# 51D.net
KiCad netlist of a schematic drawn in Altium Designer
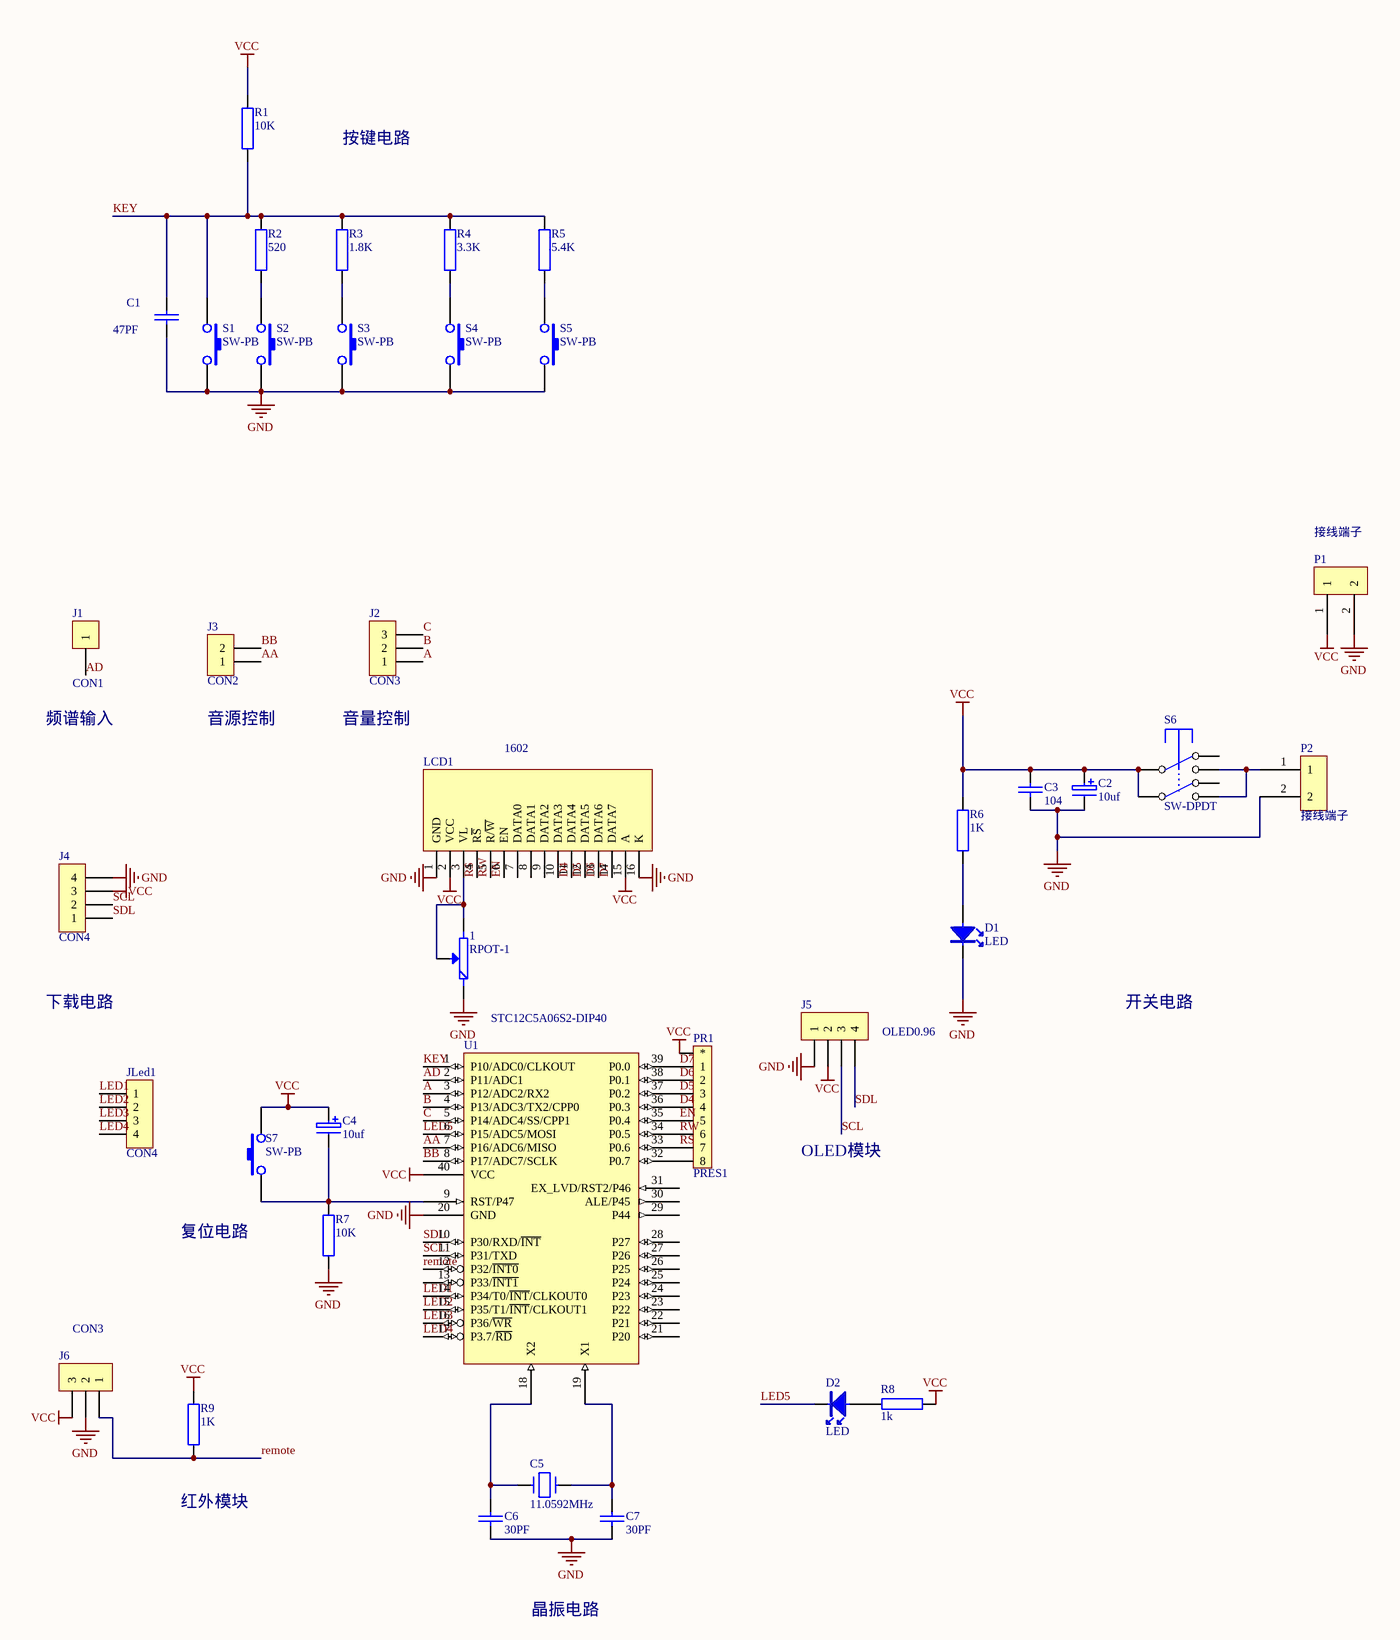
[diagram p0: 51D.SchDoc]

(export (version "E")
  (design (tool "Eeschema 10.0.6"))
  (components
    (comp (ref "1")
      (value "RPOT-1")
      (footprint "RVR-2")
      (description "普通电位器")
      (libsource (lib "电阻") (part "RPOT-1"))
    )
    (comp (ref "C1") (value "47PF") (footprint "CAP2") (libsource (lib "电容") (part "CAP1")))
    (comp (ref "C2") (value "10uf") (footprint "CAO2") (libsource (lib "电容") (part "CAP3")))
    (comp (ref "C3") (value "104") (footprint "CAP2") (libsource (lib "电容") (part "CAP1")))
    (comp (ref "C4") (value "10uf") (footprint "CAO2") (libsource (lib "电容") (part "CAP3")))
    (comp (ref "C5") (value "11.0592MHz") (footprint "XTAL1") (libsource (lib "晶振") (part "CPY")))
    (comp (ref "C6") (value "30PF") (footprint "CAP2") (libsource (lib "电容") (part "CAP1")))
    (comp (ref "C7") (value "30PF") (footprint "CAP2") (libsource (lib "电容") (part "CAP1")))
    (comp (ref "D1") (value "LED") (footprint "LED2_B") (libsource (lib "二极管") (part "LED")))
    (comp (ref "D2") (value "LED") (footprint "LED2_B") (libsource (lib "二极管") (part "LED")))
    (comp (ref "J1")
      (value "CON1")
      (footprint "SIP-1")
      (description "Connector")
      (libsource (lib "排针") (part "CON1"))
    )
    (comp (ref "J2")
      (value "CON3")
      (footprint "sip-3")
      (description "Connector")
      (libsource (lib "排针") (part "CON3"))
    )
    (comp (ref "J3")
      (value "CON2")
      (footprint "sip-2")
      (description "Connector")
      (libsource (lib "排针") (part "CON2"))
    )
    (comp (ref "J4")
      (value "CON4")
      (footprint "sip-4")
      (description "Connector")
      (libsource (lib "排针") (part "CON4"))
    )
    (comp (ref "J5")
      (value "OLED0.96")
      (footprint "sip-4")
      (description "Connector")
      (libsource (lib "") (part "CON4_1"))
    )
    (comp (ref "J6")
      (value "CON3")
      (footprint "sip-3")
      (description "Connector")
      (libsource (lib "") (part "CON3_1"))
    )
    (comp (ref "JLed1")
      (value "CON4")
      (footprint "sip-4")
      (description "Connector")
      (libsource (lib "") (part "CON4_2"))
    )
    (comp (ref "LCD1") (value "1602") (footprint "1602") (libsource (lib "液晶_数码管") (part "1602")))
    (comp (ref "P1") (value "接线端子") (footprint "音频功放自画库:接线端子") (libsource (lib "") (part "接线端子_1")))
    (comp (ref "P2") (value "接线端子") (footprint "音频功放自画库:接线端子") (libsource (lib "音频功放自画库") (part "接线端子")))
    (comp (ref "PR1") (value "PRES1") (footprint "RP1") (libsource (lib "电阻") (part "PRES1")))
    (comp (ref "R1")
      (value "10K")
      (footprint "AXIAL0.4")
      (description "电阻")
      (libsource (lib "电阻") (part "RES"))
    )
    (comp (ref "R2")
      (value "520")
      (footprint "AXIAL0.4")
      (description "电阻")
      (libsource (lib "电阻") (part "RES"))
    )
    (comp (ref "R3")
      (value "1.8K")
      (footprint "AXIAL0.4")
      (description "电阻")
      (libsource (lib "电阻") (part "RES"))
    )
    (comp (ref "R4")
      (value "3.3K")
      (footprint "AXIAL0.4")
      (description "电阻")
      (libsource (lib "电阻") (part "RES"))
    )
    (comp (ref "R5")
      (value "5.4K")
      (footprint "AXIAL0.4")
      (description "电阻")
      (libsource (lib "电阻") (part "RES"))
    )
    (comp (ref "R6")
      (value "1K")
      (footprint "AXIAL0.4")
      (description "电阻")
      (libsource (lib "电阻") (part "RES"))
    )
    (comp (ref "R7")
      (value "10K")
      (footprint "AXIAL0.4")
      (description "电阻")
      (libsource (lib "电阻") (part "RES"))
    )
    (comp (ref "R8")
      (value "1k")
      (footprint "AXIAL0.4")
      (description "电阻")
      (libsource (lib "电阻") (part "RES"))
    )
    (comp (ref "R9")
      (value "1K")
      (footprint "AXIAL0.4")
      (description "电阻")
      (libsource (lib "电阻") (part "RES"))
    )
    (comp (ref "S1") (value "SW-PB") (footprint "SW6*6") (libsource (lib "开关") (part "SW-PB")))
    (comp (ref "S2") (value "SW-PB") (footprint "SW6*6") (libsource (lib "开关") (part "SW-PB")))
    (comp (ref "S3") (value "SW-PB") (footprint "SW6*6") (libsource (lib "开关") (part "SW-PB")))
    (comp (ref "S4") (value "SW-PB") (footprint "SW6*6") (libsource (lib "开关") (part "SW-PB")))
    (comp (ref "S5") (value "SW-PB") (footprint "SW6*6") (libsource (lib "开关") (part "SW-PB")))
    (comp (ref "S6") (value "SW-DPDT") (footprint "SWH8*8") (libsource (lib "开关") (part "SW-DPDT")))
    (comp (ref "S7") (value "SW-PB") (footprint "SW6*6") (libsource (lib "开关") (part "SW-PB")))
    (comp (ref "U1")
      (value "STC12C5A06S2-DIP40")
      (footprint "DIP-40")
      (libsource (lib "单片机") (part "STC12C5A06S2-DIP40"))
    )
  )
  (nets
    (net (code "1") (name "/A") (class "Default")
      (node (ref "J2") (pin "1") (pinfunction "1_1") (pintype "passive"))
      (node (ref "U1") (pin "3") (pinfunction "P12/ADC2/RX2_3") (pintype "bidirectional"))
    )
    (net (code "2") (name "/AA") (class "Default")
      (node (ref "J3") (pin "1") (pinfunction "1_1") (pintype "passive"))
      (node (ref "U1") (pin "7") (pinfunction "P16/ADC6/MISO_7") (pintype "bidirectional"))
    )
    (net (code "3") (name "/AD") (class "Default")
      (node (ref "J1") (pin "1") (pinfunction "1_1") (pintype "passive"))
      (node (ref "U1") (pin "2") (pinfunction "P11/ADC1_2") (pintype "bidirectional"))
    )
    (net (code "4") (name "/B") (class "Default")
      (node (ref "J2") (pin "2") (pinfunction "2_2") (pintype "passive"))
      (node (ref "U1") (pin "4") (pinfunction "P13/ADC3/TX2/CPP0_4") (pintype "bidirectional"))
    )
    (net (code "5") (name "/BB") (class "Default")
      (node (ref "J3") (pin "2") (pinfunction "2_2") (pintype "passive"))
      (node (ref "U1") (pin "8") (pinfunction "P17/ADC7/SCLK_8") (pintype "bidirectional"))
    )
    (net (code "6") (name "/C") (class "Default")
      (node (ref "J2") (pin "3") (pinfunction "3_3") (pintype "passive"))
      (node (ref "U1") (pin "5") (pinfunction "P14/ADC4/SS/CPP1_5") (pintype "bidirectional"))
    )
    (net (code "7") (name "/D4") (class "Default")
      (node (ref "LCD1") (pin "11") (pinfunction "DATA4_11") (pintype "passive"))
      (node (ref "PR1") (pin "5") (pinfunction "4_5") (pintype "passive"))
      (node (ref "U1") (pin "36") (pinfunction "P0.3_36") (pintype "bidirectional"))
    )
    (net (code "8") (name "/D5") (class "Default")
      (node (ref "LCD1") (pin "12") (pinfunction "DATA5_12") (pintype "passive"))
      (node (ref "PR1") (pin "4") (pinfunction "3_4") (pintype "passive"))
      (node (ref "U1") (pin "37") (pinfunction "P0.2_37") (pintype "bidirectional"))
    )
    (net (code "9") (name "/D6") (class "Default")
      (node (ref "LCD1") (pin "13") (pinfunction "DATA6_13") (pintype "passive"))
      (node (ref "PR1") (pin "3") (pinfunction "2_3") (pintype "passive"))
      (node (ref "U1") (pin "38") (pinfunction "P0.1_38") (pintype "bidirectional"))
    )
    (net (code "10") (name "/D7") (class "Default")
      (node (ref "LCD1") (pin "14") (pinfunction "DATA7_14") (pintype "passive"))
      (node (ref "PR1") (pin "2") (pinfunction "1_2") (pintype "passive"))
      (node (ref "U1") (pin "39") (pinfunction "P0.0_39") (pintype "bidirectional"))
    )
    (net (code "11") (name "/EN") (class "Default")
      (node (ref "LCD1") (pin "6") (pinfunction "EN_6") (pintype "passive"))
      (node (ref "PR1") (pin "6") (pinfunction "5_6") (pintype "passive"))
      (node (ref "U1") (pin "35") (pinfunction "P0.4_35") (pintype "bidirectional"))
    )
    (net (code "12") (name "/KEY") (class "Default")
      (node (ref "C1") (pin "1") (pinfunction "1_1") (pintype "passive"))
      (node (ref "R1") (pin "1") (pinfunction "1_1") (pintype "passive"))
      (node (ref "R2") (pin "2") (pinfunction "2_2") (pintype "passive"))
      (node (ref "R3") (pin "2") (pinfunction "2_2") (pintype "passive"))
      (node (ref "R4") (pin "2") (pinfunction "2_2") (pintype "passive"))
      (node (ref "R5") (pin "2") (pinfunction "2_2") (pintype "passive"))
      (node (ref "S1") (pin "1") (pinfunction "1_1") (pintype "passive"))
      (node (ref "U1") (pin "1") (pinfunction "P10/ADC0/CLKOUT_1") (pintype "bidirectional"))
    )
    (net (code "13") (name "/LED1") (class "Default")
      (node (ref "JLed1") (pin "1") (pinfunction "1_1") (pintype "passive"))
      (node (ref "U1") (pin "14") (pinfunction "P34/T0/~{INT}/CLKOUT0_14") (pintype "bidirectional"))
    )
    (net (code "14") (name "/LED2") (class "Default")
      (node (ref "JLed1") (pin "2") (pinfunction "2_2") (pintype "passive"))
      (node (ref "U1") (pin "15") (pinfunction "P35/T1/~{INT}/CLKOUT1_15") (pintype "bidirectional"))
    )
    (net (code "15") (name "/LED3") (class "Default")
      (node (ref "JLed1") (pin "3") (pinfunction "3_3") (pintype "passive"))
      (node (ref "U1") (pin "16") (pinfunction "P36/~{WR}_16") (pintype "bidirectional"))
    )
    (net (code "16") (name "/LED4") (class "Default")
      (node (ref "JLed1") (pin "4") (pinfunction "4_4") (pintype "passive"))
      (node (ref "U1") (pin "17") (pinfunction "P3.7/~{RD}_17") (pintype "bidirectional"))
    )
    (net (code "17") (name "/LED5") (class "Default")
      (node (ref "D2") (pin "2") (pinfunction "2_2") (pintype "passive"))
      (node (ref "U1") (pin "6") (pinfunction "P15/ADC5/MOSI_6") (pintype "bidirectional"))
    )
    (net (code "18") (name "/RS") (class "Default")
      (node (ref "LCD1") (pin "4") (pinfunction "R~{S}_4") (pintype "passive"))
      (node (ref "PR1") (pin "8") (pinfunction "7_8") (pintype "passive"))
      (node (ref "U1") (pin "33") (pinfunction "P0.6_33") (pintype "bidirectional"))
    )
    (net (code "19") (name "/RW") (class "Default")
      (node (ref "LCD1") (pin "5") (pinfunction "R/~{W}_5") (pintype "passive"))
      (node (ref "PR1") (pin "7") (pinfunction "6_7") (pintype "passive"))
      (node (ref "U1") (pin "34") (pinfunction "P0.5_34") (pintype "bidirectional"))
    )
    (net (code "20") (name "/SCL") (class "Default")
      (node (ref "J4") (pin "2") (pinfunction "2_2") (pintype "passive"))
      (node (ref "J5") (pin "3") (pinfunction "3_3") (pintype "passive"))
      (node (ref "U1") (pin "11") (pinfunction "P31/TXD_11") (pintype "bidirectional"))
    )
    (net (code "21") (name "/SDL") (class "Default")
      (node (ref "J4") (pin "1") (pinfunction "1_1") (pintype "passive"))
      (node (ref "J5") (pin "4") (pinfunction "4_4") (pintype "passive"))
      (node (ref "U1") (pin "10") (pinfunction "P30/RXD/~{INT}_10") (pintype "bidirectional"))
    )
    (net (code "22") (name "/remote") (class "Default")
      (node (ref "J6") (pin "1") (pinfunction "1_1") (pintype "passive"))
      (node (ref "R9") (pin "1") (pinfunction "1_1") (pintype "passive"))
      (node (ref "U1") (pin "12") (pinfunction "P32/~{INT0}_12") (pintype "bidirectional"))
    )
    (net (code "23") (name "GND") (class "Default")
      (node (ref "1") (pin "1") (pinfunction "1_1") (pintype "passive"))
      (node (ref "C1") (pin "2") (pinfunction "2_2") (pintype "passive"))
      (node (ref "C2") (pin "2") (pintype "passive"))
      (node (ref "C3") (pin "2") (pinfunction "2_2") (pintype "passive"))
      (node (ref "C6") (pin "2") (pinfunction "2_2") (pintype "passive"))
      (node (ref "C7") (pin "2") (pinfunction "2_2") (pintype "passive"))
      (node (ref "D1") (pin "2") (pinfunction "2_2") (pintype "passive"))
      (node (ref "J4") (pin "4") (pinfunction "4_4") (pintype "passive"))
      (node (ref "J5") (pin "1") (pinfunction "1_1") (pintype "passive"))
      (node (ref "J6") (pin "2") (pinfunction "2_2") (pintype "passive"))
      (node (ref "LCD1") (pin "1") (pinfunction "GND_1") (pintype "passive"))
      (node (ref "LCD1") (pin "16") (pinfunction "K_16") (pintype "passive"))
      (node (ref "P1") (pin "2") (pinfunction "2_2") (pintype "passive"))
      (node (ref "P2") (pin "2") (pinfunction "2_2") (pintype "passive"))
      (node (ref "R7") (pin "1") (pinfunction "1_1") (pintype "passive"))
      (node (ref "S1") (pin "2") (pinfunction "2_2") (pintype "passive"))
      (node (ref "S2") (pin "2") (pinfunction "2_2") (pintype "passive"))
      (node (ref "S3") (pin "2") (pinfunction "2_2") (pintype "passive"))
      (node (ref "S4") (pin "2") (pinfunction "2_2") (pintype "passive"))
      (node (ref "S5") (pin "2") (pinfunction "2_2") (pintype "passive"))
      (node (ref "U1") (pin "20") (pinfunction "GND_20") (pintype "power_in"))
    )
    (net (code "24") (name "Net-(1-M)") (class "Default")
      (node (ref "1") (pin "2") (pinfunction "M_2") (pintype "passive"))
      (node (ref "1") (pin "3") (pinfunction "3_3") (pintype "passive"))
      (node (ref "LCD1") (pin "3") (pinfunction "VL_3") (pintype "passive"))
    )
    (net (code "25") (name "Net-(D1-Pad1)") (class "Default")
      (node (ref "D1") (pin "1") (pinfunction "1_1") (pintype "passive"))
      (node (ref "R6") (pin "1") (pinfunction "1_1") (pintype "passive"))
    )
    (net (code "26") (name "Net-(D2-Pad1)") (class "Default")
      (node (ref "D2") (pin "1") (pinfunction "1_1") (pintype "passive"))
      (node (ref "R8") (pin "2") (pinfunction "2_2") (pintype "passive"))
    )
    (net (code "27") (name "Net-(P2-Pad1)") (class "Default")
      (node (ref "P2") (pin "1") (pinfunction "1_1") (pintype "passive"))
      (node (ref "S6") (pin "3") (pinfunction "3_3") (pintype "passive"))
      (node (ref "S6") (pin "4") (pinfunction "4_4") (pintype "passive"))
    )
    (net (code "28") (name "Net-(PR1-8)") (class "Default")
      (node (ref "PR1") (pin "9") (pinfunction "8_9") (pintype "passive"))
      (node (ref "U1") (pin "32") (pinfunction "P0.7_32") (pintype "bidirectional"))
    )
    (net (code "29") (name "Net-(R2-Pad1)") (class "Default")
      (node (ref "R2") (pin "1") (pinfunction "1_1") (pintype "passive"))
      (node (ref "S2") (pin "1") (pinfunction "1_1") (pintype "passive"))
    )
    (net (code "30") (name "Net-(R3-Pad1)") (class "Default")
      (node (ref "R3") (pin "1") (pinfunction "1_1") (pintype "passive"))
      (node (ref "S3") (pin "1") (pinfunction "1_1") (pintype "passive"))
    )
    (net (code "31") (name "Net-(R4-Pad1)") (class "Default")
      (node (ref "R4") (pin "1") (pinfunction "1_1") (pintype "passive"))
      (node (ref "S4") (pin "1") (pinfunction "1_1") (pintype "passive"))
    )
    (net (code "32") (name "Net-(R5-Pad1)") (class "Default")
      (node (ref "R5") (pin "1") (pinfunction "1_1") (pintype "passive"))
      (node (ref "S5") (pin "1") (pinfunction "1_1") (pintype "passive"))
    )
    (net (code "33") (name "Net-(U1-RST{slash}P47)") (class "Default")
      (node (ref "C4") (pin "2") (pintype "passive"))
      (node (ref "R7") (pin "2") (pinfunction "2_2") (pintype "passive"))
      (node (ref "S7") (pin "1") (pinfunction "1_1") (pintype "passive"))
      (node (ref "U1") (pin "9") (pinfunction "RST/P47_9") (pintype "input"))
    )
    (net (code "34") (name "Net-(U1-X1)") (class "Default")
      (node (ref "C5") (pin "2") (pintype "passive"))
      (node (ref "C7") (pin "1") (pinfunction "1_1") (pintype "passive"))
      (node (ref "U1") (pin "19") (pinfunction "X1_19") (pintype "input"))
    )
    (net (code "35") (name "Net-(U1-X2)") (class "Default")
      (node (ref "C5") (pin "1") (pintype "passive"))
      (node (ref "C6") (pin "1") (pinfunction "1_1") (pintype "passive"))
      (node (ref "U1") (pin "18") (pinfunction "X2_18") (pintype "input"))
    )
    (net (code "36") (name "VCC") (class "Default")
      (node (ref "C2") (pin "1") (pintype "passive"))
      (node (ref "C3") (pin "1") (pinfunction "1_1") (pintype "passive"))
      (node (ref "C4") (pin "1") (pintype "passive"))
      (node (ref "J4") (pin "3") (pinfunction "3_3") (pintype "passive"))
      (node (ref "J5") (pin "2") (pinfunction "2_2") (pintype "passive"))
      (node (ref "J6") (pin "3") (pinfunction "3_3") (pintype "passive"))
      (node (ref "LCD1") (pin "15") (pinfunction "A_15") (pintype "passive"))
      (node (ref "LCD1") (pin "2") (pinfunction "VCC_2") (pintype "passive"))
      (node (ref "P1") (pin "1") (pinfunction "1_1") (pintype "passive"))
      (node (ref "PR1") (pin "1") (pinfunction "*_1") (pintype "passive"))
      (node (ref "R1") (pin "2") (pinfunction "2_2") (pintype "passive"))
      (node (ref "R6") (pin "2") (pinfunction "2_2") (pintype "passive"))
      (node (ref "R8") (pin "1") (pinfunction "1_1") (pintype "passive"))
      (node (ref "R9") (pin "2") (pinfunction "2_2") (pintype "passive"))
      (node (ref "S6") (pin "2") (pinfunction "2_2") (pintype "passive"))
      (node (ref "S6") (pin "5") (pinfunction "5_5") (pintype "passive"))
      (node (ref "S7") (pin "2") (pinfunction "2_2") (pintype "passive"))
      (node (ref "U1") (pin "40") (pinfunction "VCC_40") (pintype "power_in"))
    )
    (net (code "37") (name "unconnected-(LCD1-DATA0-Pad7)") (class "Default")
      (node (ref "LCD1") (pin "7") (pinfunction "DATA0_7") (pintype "passive"))
    )
    (net (code "38") (name "unconnected-(LCD1-DATA1-Pad8)") (class "Default")
      (node (ref "LCD1") (pin "8") (pinfunction "DATA1_8") (pintype "passive"))
    )
    (net (code "39") (name "unconnected-(LCD1-DATA2-Pad9)") (class "Default")
      (node (ref "LCD1") (pin "9") (pinfunction "DATA2_9") (pintype "passive"))
    )
    (net (code "40") (name "unconnected-(LCD1-DATA3-Pad10)") (class "Default")
      (node (ref "LCD1") (pin "10") (pinfunction "DATA3_10") (pintype "passive"))
    )
    (net (code "41") (name "unconnected-(S6-Pad1)") (class "Default")
      (node (ref "S6") (pin "1") (pinfunction "1_1") (pintype "passive"))
    )
    (net (code "42") (name "unconnected-(S6-Pad6)") (class "Default")
      (node (ref "S6") (pin "6") (pinfunction "6_6") (pintype "passive"))
    )
    (net (code "43") (name "unconnected-(U1-ALE{slash}P45-Pad30)") (class "Default")
      (node (ref "U1") (pin "30") (pinfunction "ALE/P45_30") (pintype "output"))
    )
    (net (code "44") (name "unconnected-(U1-EX_LVD{slash}RST2{slash}P46-Pad31)") (class "Default")
      (node (ref "U1") (pin "31") (pinfunction "EX_LVD/RST2/P46_31") (pintype "input"))
    )
    (net (code "45") (name "unconnected-(U1-P20-Pad21)") (class "Default")
      (node (ref "U1") (pin "21") (pinfunction "P20_21") (pintype "bidirectional"))
    )
    (net (code "46") (name "unconnected-(U1-P21-Pad22)") (class "Default")
      (node (ref "U1") (pin "22") (pinfunction "P21_22") (pintype "bidirectional"))
    )
    (net (code "47") (name "unconnected-(U1-P22-Pad23)") (class "Default")
      (node (ref "U1") (pin "23") (pinfunction "P22_23") (pintype "bidirectional"))
    )
    (net (code "48") (name "unconnected-(U1-P23-Pad24)") (class "Default")
      (node (ref "U1") (pin "24") (pinfunction "P23_24") (pintype "bidirectional"))
    )
    (net (code "49") (name "unconnected-(U1-P24-Pad25)") (class "Default")
      (node (ref "U1") (pin "25") (pinfunction "P24_25") (pintype "bidirectional"))
    )
    (net (code "50") (name "unconnected-(U1-P25-Pad26)") (class "Default")
      (node (ref "U1") (pin "26") (pinfunction "P25_26") (pintype "bidirectional"))
    )
    (net (code "51") (name "unconnected-(U1-P26-Pad27)") (class "Default")
      (node (ref "U1") (pin "27") (pinfunction "P26_27") (pintype "bidirectional"))
    )
    (net (code "52") (name "unconnected-(U1-P27-Pad28)") (class "Default")
      (node (ref "U1") (pin "28") (pinfunction "P27_28") (pintype "bidirectional"))
    )
    (net (code "53") (name "unconnected-(U1-P33{slash}~{INT1}-Pad13)") (class "Default")
      (node (ref "U1") (pin "13") (pinfunction "P33/~{INT1}_13") (pintype "bidirectional"))
    )
    (net (code "54") (name "unconnected-(U1-P44-Pad29)") (class "Default")
      (node (ref "U1") (pin "29") (pinfunction "P44_29") (pintype "output"))
    )
  )
)
